# CAPACITOR.net
KiCad netlist of a schematic drawn in Altium Designer
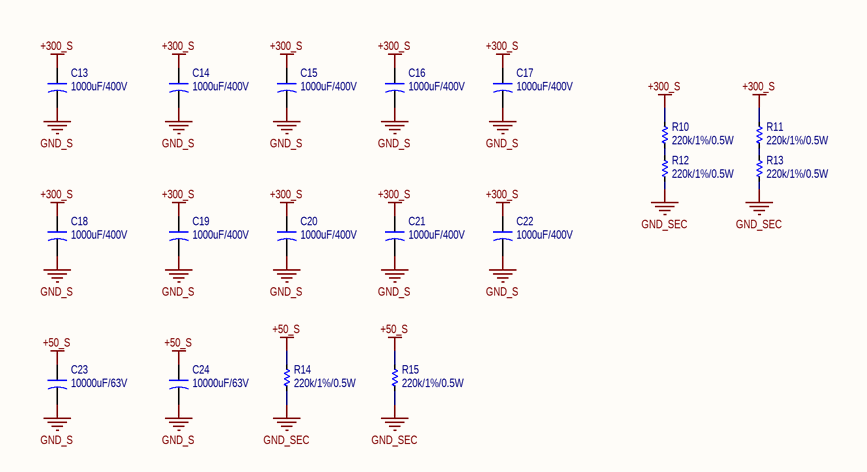
[diagram p0: CAPACITOR.SchDoc]

(export (version "E")
  (design (tool "Eeschema 10.0.6"))
  (components
    (comp (ref "C13")
      (value "1000uF/400V")
      (footprint "CA-ALU-35x50")
      (description "NO PN")
      (fields (field (name "PUBLISHER") "Altium Limited"))
      (libsource (lib "Library") (part "CN-ALU-DIP"))
    )
    (comp (ref "C14")
      (value "1000uF/400V")
      (footprint "CA-ALU-35x50")
      (description "NO PN")
      (fields (field (name "PUBLISHER") "Altium Limited"))
      (libsource (lib "Library") (part "CN-ALU-DIP"))
    )
    (comp (ref "C15")
      (value "1000uF/400V")
      (footprint "CA-ALU-35x50")
      (description "NO PN")
      (fields (field (name "PUBLISHER") "Altium Limited"))
      (libsource (lib "Library") (part "CN-ALU-DIP"))
    )
    (comp (ref "C16")
      (value "1000uF/400V")
      (footprint "CA-ALU-35x50")
      (description "NO PN")
      (fields (field (name "PUBLISHER") "Altium Limited"))
      (libsource (lib "Library") (part "CN-ALU-DIP"))
    )
    (comp (ref "C17")
      (value "1000uF/400V")
      (footprint "CA-ALU-35x50")
      (description "NO PN")
      (fields (field (name "PUBLISHER") "Altium Limited"))
      (libsource (lib "Library") (part "CN-ALU-DIP"))
    )
    (comp (ref "C18")
      (value "1000uF/400V")
      (footprint "CA-ALU-35x50")
      (description "NO PN")
      (fields (field (name "PUBLISHER") "Altium Limited"))
      (libsource (lib "Library") (part "CN-ALU-DIP"))
    )
    (comp (ref "C19")
      (value "1000uF/400V")
      (footprint "CA-ALU-35x50")
      (description "NO PN")
      (fields (field (name "PUBLISHER") "Altium Limited"))
      (libsource (lib "Library") (part "CN-ALU-DIP"))
    )
    (comp (ref "C20")
      (value "1000uF/400V")
      (footprint "CA-ALU-35x50")
      (description "NO PN")
      (fields (field (name "PUBLISHER") "Altium Limited"))
      (libsource (lib "Library") (part "CN-ALU-DIP"))
    )
    (comp (ref "C21")
      (value "1000uF/400V")
      (footprint "CA-ALU-35x50")
      (description "NO PN")
      (fields (field (name "PUBLISHER") "Altium Limited"))
      (libsource (lib "Library") (part "CN-ALU-DIP"))
    )
    (comp (ref "C22")
      (value "1000uF/400V")
      (footprint "CA-ALU-35x50")
      (description "NO PN")
      (fields (field (name "PUBLISHER") "Altium Limited"))
      (libsource (lib "Library") (part "CN-ALU-DIP"))
    )
    (comp (ref "C23")
      (value "10000uF/63V")
      (footprint "CA-ALU-35x50")
      (description "NO PN")
      (fields (field (name "PUBLISHER") "Altium Limited"))
      (libsource (lib "Library") (part "CN-ALU-DIP"))
    )
    (comp (ref "C24")
      (value "10000uF/63V")
      (footprint "CA-ALU-35x50")
      (description "NO PN")
      (fields (field (name "PUBLISHER") "Altium Limited"))
      (libsource (lib "Library") (part "CN-ALU-DIP"))
    )
    (comp (ref "R10")
      (value "220k/1%/0.5W")
      (footprint "RES-SMD-2010")
      (description "CHV2010-FX-2203ELF")
      (fields
        (field (name "MANUFACTURER") "Generic Components")
        (field (name "PUBLISHER") "Altium Hobart Technology Centre")
      )
      (libsource (lib "Library") (part "Res-SMD"))
    )
    (comp (ref "R11")
      (value "220k/1%/0.5W")
      (footprint "RES-SMD-2010")
      (description "CHV2010-FX-2203ELF")
      (fields
        (field (name "MANUFACTURER") "Generic Components")
        (field (name "PUBLISHER") "Altium Hobart Technology Centre")
      )
      (libsource (lib "Library") (part "Res-SMD"))
    )
    (comp (ref "R12")
      (value "220k/1%/0.5W")
      (footprint "RES-SMD-2010")
      (description "CHV2010-FX-2203ELF")
      (fields
        (field (name "MANUFACTURER") "Generic Components")
        (field (name "PUBLISHER") "Altium Hobart Technology Centre")
      )
      (libsource (lib "Library") (part "Res-SMD"))
    )
    (comp (ref "R13")
      (value "220k/1%/0.5W")
      (footprint "RES-SMD-2010")
      (description "CHV2010-FX-2203ELF")
      (fields
        (field (name "MANUFACTURER") "Generic Components")
        (field (name "PUBLISHER") "Altium Hobart Technology Centre")
      )
      (libsource (lib "Library") (part "Res-SMD"))
    )
    (comp (ref "R14")
      (value "220k/1%/0.5W")
      (footprint "RES-SMD-2010")
      (description "CHV2010-FX-2203ELF")
      (fields
        (field (name "MANUFACTURER") "Generic Components")
        (field (name "PUBLISHER") "Altium Hobart Technology Centre")
      )
      (libsource (lib "Library") (part "Res-SMD"))
    )
    (comp (ref "R15")
      (value "220k/1%/0.5W")
      (footprint "RES-SMD-2010")
      (description "CHV2010-FX-2203ELF")
      (fields
        (field (name "MANUFACTURER") "Generic Components")
        (field (name "PUBLISHER") "Altium Hobart Technology Centre")
      )
      (libsource (lib "Library") (part "Res-SMD"))
    )
  )
  (nets
    (net (code "1") (name "+50_S") (class "Default")
      (node (ref "C23") (pin "1") (pinfunction "1_1") (pintype "passive"))
      (node (ref "C24") (pin "1") (pinfunction "1_1") (pintype "passive"))
      (node (ref "R14") (pin "1") (pinfunction "1_1") (pintype "passive"))
      (node (ref "R15") (pin "1") (pinfunction "1_1") (pintype "passive"))
    )
    (net (code "2") (name "+300_S") (class "Default")
      (node (ref "C13") (pin "1") (pinfunction "1_1") (pintype "passive"))
      (node (ref "C14") (pin "1") (pinfunction "1_1") (pintype "passive"))
      (node (ref "C15") (pin "1") (pinfunction "1_1") (pintype "passive"))
      (node (ref "C16") (pin "1") (pinfunction "1_1") (pintype "passive"))
      (node (ref "C17") (pin "1") (pinfunction "1_1") (pintype "passive"))
      (node (ref "C18") (pin "1") (pinfunction "1_1") (pintype "passive"))
      (node (ref "C19") (pin "1") (pinfunction "1_1") (pintype "passive"))
      (node (ref "C20") (pin "1") (pinfunction "1_1") (pintype "passive"))
      (node (ref "C21") (pin "1") (pinfunction "1_1") (pintype "passive"))
      (node (ref "C22") (pin "1") (pinfunction "1_1") (pintype "passive"))
      (node (ref "R10") (pin "1") (pinfunction "1_1") (pintype "passive"))
      (node (ref "R11") (pin "1") (pinfunction "1_1") (pintype "passive"))
    )
    (net (code "3") (name "GND_S") (class "Default")
      (node (ref "C13") (pin "2") (pinfunction "2_2") (pintype "passive"))
      (node (ref "C14") (pin "2") (pinfunction "2_2") (pintype "passive"))
      (node (ref "C15") (pin "2") (pinfunction "2_2") (pintype "passive"))
      (node (ref "C16") (pin "2") (pinfunction "2_2") (pintype "passive"))
      (node (ref "C17") (pin "2") (pinfunction "2_2") (pintype "passive"))
      (node (ref "C18") (pin "2") (pinfunction "2_2") (pintype "passive"))
      (node (ref "C19") (pin "2") (pinfunction "2_2") (pintype "passive"))
      (node (ref "C20") (pin "2") (pinfunction "2_2") (pintype "passive"))
      (node (ref "C21") (pin "2") (pinfunction "2_2") (pintype "passive"))
      (node (ref "C22") (pin "2") (pinfunction "2_2") (pintype "passive"))
      (node (ref "C23") (pin "2") (pinfunction "2_2") (pintype "passive"))
      (node (ref "C24") (pin "2") (pinfunction "2_2") (pintype "passive"))
    )
    (net (code "4") (name "GND_SEC") (class "Default")
      (node (ref "R12") (pin "2") (pinfunction "2_2") (pintype "passive"))
      (node (ref "R13") (pin "2") (pinfunction "2_2") (pintype "passive"))
      (node (ref "R14") (pin "2") (pinfunction "2_2") (pintype "passive"))
      (node (ref "R15") (pin "2") (pinfunction "2_2") (pintype "passive"))
    )
    (net (code "5") (name "Net-(R10-Pad2)") (class "Default")
      (node (ref "R10") (pin "2") (pinfunction "2_2") (pintype "passive"))
      (node (ref "R12") (pin "1") (pinfunction "1_1") (pintype "passive"))
    )
    (net (code "6") (name "Net-(R11-Pad2)") (class "Default")
      (node (ref "R11") (pin "2") (pinfunction "2_2") (pintype "passive"))
      (node (ref "R13") (pin "1") (pinfunction "1_1") (pintype "passive"))
    )
  )
)
